# Temp_Mux.net
KiCad netlist of a schematic drawn in Altium Designer
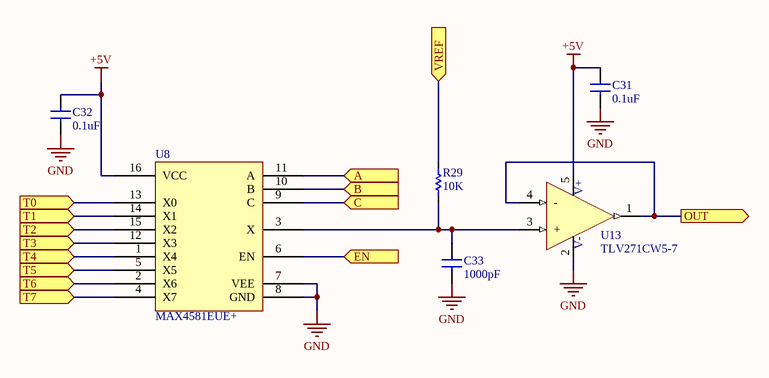
[diagram p0: Temp_Mux.SchDoc]

(export (version "E")
  (design (tool "Eeschema 10.0.6"))
  (components
    (comp (ref "C31")
      (value "0.1uF")
      (footprint "0402_CAPACITOR")
      (description "CAP CERM 0.1uF 10% 16V 0402")
      (fields (field (name "VOLTAGE") "16V") (field (name "Comment") "CAP 0.1uF 16V X7R"))
      (libsource (lib "capacitor") (part "C_0402_0.1uF_16V_10%"))
    )
    (comp (ref "C32")
      (value "0.1uF")
      (footprint "0402_CAPACITOR")
      (description "CAP CERM 0.1uF 10% 16V 0402")
      (fields (field (name "VOLTAGE") "16V") (field (name "Comment") "CAP 0.1uF 16V X7R"))
      (libsource (lib "capacitor") (part "C_0402_0.1uF_16V_10%"))
    )
    (comp (ref "C33")
      (value "1000pF")
      (footprint "0402_CAPACITOR")
      (fields
        (field (name "VOLTAGE") "50V")
        (field (name "MANUFACTURER") "Samsung")
        (field (name "MANUFACTURER PART NUMBER") "CL05CJB5NNNC")
      )
      (libsource (lib "capacitor") (part "C_0402_generic_C0G/NP0_50V_5%"))
    )
    (comp (ref "R29")
      (value "10K")
      (footprint "0402_Resistor")
      (description "Generic 0402 Resistor (10.2R to 10M)")
      (fields (field (name "TOLERANCE") "±1%") (field (name "MANUFACTURER") "Yageo"))
      (libsource (lib "resistor") (part "R_0402_generic_1%"))
    )
    (comp (ref "U8")
      (value "MAX4581EUE+")
      (footprint "TSSOP-16")
      (description "1 Circuit IC Switch 8:1 80 Ohm 16-TSSOP")
      (libsource (lib "ic") (part "U_MAX4581"))
    )
    (comp (ref "U13")
      (value "TLV271CW5-7")
      (footprint "SOT23-5")
      (description "CMOS Amplifier 1 Circuit Rail-to-Rail SOT-25")
      (fields (field (name "MANUFACTURER") "Diodes"))
      (libsource (lib "ic") (part "U_TLV271"))
    )
  )
  (nets
    (net (code "1") (name "+5V") (class "Default")
      (node (ref "C31") (pin "1") (pinfunction "1_1") (pintype "passive"))
      (node (ref "C32") (pin "1") (pinfunction "1_1") (pintype "passive"))
      (node (ref "U13") (pin "5") (pinfunction "VDD_5") (pintype "power_in"))
      (node (ref "U8") (pin "16") (pinfunction "VCC_16") (pintype "passive"))
    )
    (net (code "2") (name "/A") (class "Default")
      (node (ref "U8") (pin "11") (pinfunction "A_11") (pintype "passive"))
    )
    (net (code "3") (name "/B") (class "Default")
      (node (ref "U8") (pin "10") (pinfunction "B_10") (pintype "passive"))
    )
    (net (code "4") (name "/C") (class "Default")
      (node (ref "U8") (pin "9") (pinfunction "C_9") (pintype "passive"))
    )
    (net (code "5") (name "/EN") (class "Default")
      (node (ref "U8") (pin "6") (pinfunction "EN_6") (pintype "passive"))
    )
    (net (code "6") (name "/OUT") (class "Default")
      (node (ref "U13") (pin "1") (pinfunction "OUT_1") (pintype "output"))
      (node (ref "U13") (pin "4") (pinfunction "-_4") (pintype "input"))
    )
    (net (code "7") (name "/T0") (class "Default")
      (node (ref "U8") (pin "13") (pinfunction "X0_13") (pintype "passive"))
    )
    (net (code "8") (name "/T1") (class "Default")
      (node (ref "U8") (pin "14") (pinfunction "X1_14") (pintype "passive"))
    )
    (net (code "9") (name "/T2") (class "Default")
      (node (ref "U8") (pin "15") (pinfunction "X2_15") (pintype "passive"))
    )
    (net (code "10") (name "/T3") (class "Default")
      (node (ref "U8") (pin "12") (pinfunction "X3_12") (pintype "passive"))
    )
    (net (code "11") (name "/T4") (class "Default")
      (node (ref "U8") (pin "1") (pinfunction "X4_1") (pintype "passive"))
    )
    (net (code "12") (name "/T5") (class "Default")
      (node (ref "U8") (pin "5") (pinfunction "X5_5") (pintype "passive"))
    )
    (net (code "13") (name "/T6") (class "Default")
      (node (ref "U8") (pin "2") (pinfunction "X6_2") (pintype "passive"))
    )
    (net (code "14") (name "/T7") (class "Default")
      (node (ref "U8") (pin "4") (pinfunction "X7_4") (pintype "passive"))
    )
    (net (code "15") (name "/VREF") (class "Default")
      (node (ref "R29") (pin "2") (pinfunction "2_2") (pintype "passive"))
    )
    (net (code "16") (name "GND") (class "Default")
      (node (ref "C31") (pin "2") (pinfunction "2_2") (pintype "passive"))
      (node (ref "C32") (pin "2") (pinfunction "2_2") (pintype "passive"))
      (node (ref "C33") (pin "2") (pinfunction "2_2") (pintype "passive"))
      (node (ref "U13") (pin "2") (pinfunction "GND_2") (pintype "power_in"))
      (node (ref "U8") (pin "7") (pinfunction "VEE_7") (pintype "passive"))
      (node (ref "U8") (pin "8") (pinfunction "GND_8") (pintype "passive"))
    )
    (net (code "17") (name "Net-(U13-+)") (class "Default")
      (node (ref "C33") (pin "1") (pinfunction "1_1") (pintype "passive"))
      (node (ref "R29") (pin "1") (pinfunction "1_1") (pintype "passive"))
      (node (ref "U13") (pin "3") (pinfunction "+_3") (pintype "input"))
      (node (ref "U8") (pin "3") (pinfunction "X_3") (pintype "passive"))
    )
  )
)
